# PitchDetector.net
KiCad netlist of a schematic drawn in EAGLE
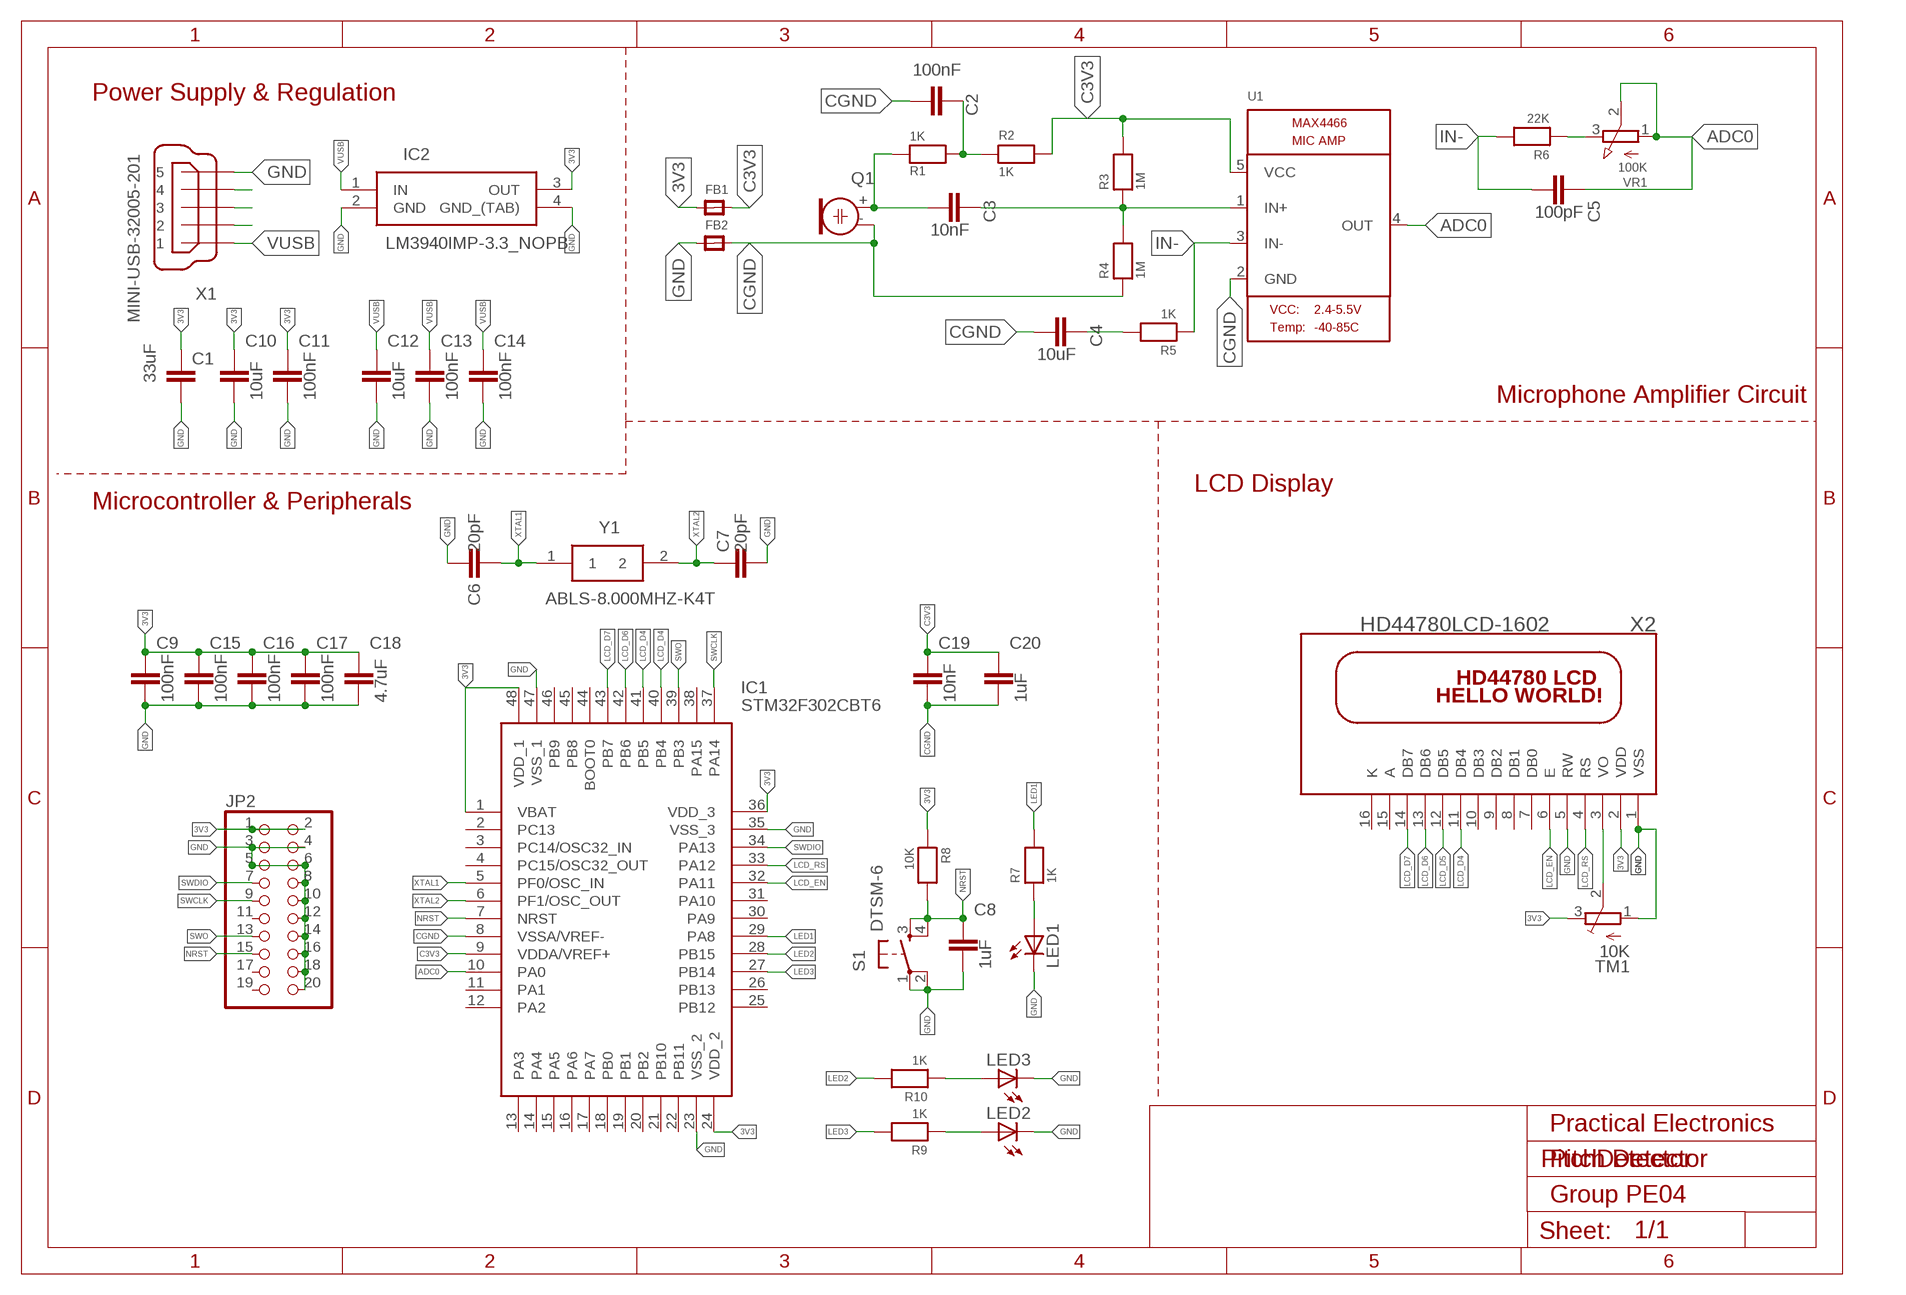
[diagram p0: schematic, sheet 1]

(export (version "E")
  (design (tool "Eeschema 10.0.6"))
  (components
    (comp (ref "C1")
      (value "33uF")
      (footprint "eagle-import:C1206K")
      (libsource (lib "eagle-import") (part "resistor_348_C-EUC1206K"))
    )
    (comp (ref "C2")
      (value "100nF")
      (footprint "eagle-import:C1206K")
      (libsource (lib "eagle-import") (part "resistor_348_C-EUC1206K"))
    )
    (comp (ref "C3")
      (value "10nF")
      (footprint "eagle-import:C1206K")
      (libsource (lib "eagle-import") (part "resistor_348_C-EUC1206K"))
    )
    (comp (ref "C4")
      (value "10uF")
      (footprint "eagle-import:C1206K")
      (libsource (lib "eagle-import") (part "resistor_348_C-EUC1206K"))
    )
    (comp (ref "C5")
      (value "100pF")
      (footprint "eagle-import:C1206K")
      (libsource (lib "eagle-import") (part "resistor_348_C-EUC1206K"))
    )
    (comp (ref "C6")
      (value "20pF")
      (footprint "eagle-import:C0805K")
      (libsource (lib "eagle-import") (part "C-EUC0805K"))
    )
    (comp (ref "C7")
      (value "20pF")
      (footprint "eagle-import:C0805K")
      (libsource (lib "eagle-import") (part "C-EUC0805K"))
    )
    (comp (ref "C8")
      (value "1uF")
      (footprint "eagle-import:C1206K")
      (libsource (lib "eagle-import") (part "resistor_348_C-EUC1206K"))
    )
    (comp (ref "C9")
      (value "100nF")
      (footprint "eagle-import:C1206K")
      (libsource (lib "eagle-import") (part "resistor_348_C-EUC1206K"))
    )
    (comp (ref "C10")
      (value "10uF")
      (footprint "eagle-import:C1206K")
      (libsource (lib "eagle-import") (part "resistor_348_C-EUC1206K"))
    )
    (comp (ref "C11")
      (value "100nF")
      (footprint "eagle-import:C1206K")
      (libsource (lib "eagle-import") (part "resistor_348_C-EUC1206K"))
    )
    (comp (ref "C12")
      (value "10uF")
      (footprint "eagle-import:C1206K")
      (libsource (lib "eagle-import") (part "resistor_348_C-EUC1206K"))
    )
    (comp (ref "C13")
      (value "100nF")
      (footprint "eagle-import:C1206K")
      (libsource (lib "eagle-import") (part "resistor_348_C-EUC1206K"))
    )
    (comp (ref "C14")
      (value "100nF")
      (footprint "eagle-import:C1206K")
      (libsource (lib "eagle-import") (part "resistor_348_C-EUC1206K"))
    )
    (comp (ref "C15")
      (value "100nF")
      (footprint "eagle-import:C1206K")
      (libsource (lib "eagle-import") (part "resistor_348_C-EUC1206K"))
    )
    (comp (ref "C16")
      (value "100nF")
      (footprint "eagle-import:C1206K")
      (libsource (lib "eagle-import") (part "resistor_348_C-EUC1206K"))
    )
    (comp (ref "C17")
      (value "100nF")
      (footprint "eagle-import:C1206K")
      (libsource (lib "eagle-import") (part "resistor_348_C-EUC1206K"))
    )
    (comp (ref "C18")
      (value "4.7uF")
      (footprint "eagle-import:C1206K")
      (libsource (lib "eagle-import") (part "resistor_348_C-EUC1206K"))
    )
    (comp (ref "C19")
      (value "10nF")
      (footprint "eagle-import:C1206K")
      (libsource (lib "eagle-import") (part "resistor_348_C-EUC1206K"))
    )
    (comp (ref "C20")
      (value "1uF")
      (footprint "eagle-import:C1206K")
      (libsource (lib "eagle-import") (part "resistor_348_C-EUC1206K"))
    )
    (comp (ref "FB1")
      (value "MICROBUILDER_FERRITE_0805")
      (footprint "eagle-import:MICROBUILDER__0805")
      (libsource (lib "eagle-import") (part "MICROBUILDER_FERRITE_0805"))
    )
    (comp (ref "FB2")
      (value "MICROBUILDER_FERRITE_0805")
      (footprint "eagle-import:MICROBUILDER__0805")
      (libsource (lib "eagle-import") (part "MICROBUILDER_FERRITE_0805"))
    )
    (comp (ref "IC1")
      (value "STM32F302CBT6")
      (footprint "eagle-import:QFP50P900X900X160-48N")
      (fields
        (field (name "MOUSER_PART_NUMBER") "511-STM32F302CBT6")
        (field (name "RS_PART_NUMBER") "8107641P")
      )
      (libsource (lib "eagle-import") (part "STM32F302CBT6"))
    )
    (comp (ref "IC2")
      (value "LM3940IMP-3.3_NOPB")
      (footprint "eagle-import:SOT230P700X180-4N")
      (fields
        (field (name "MANUFACTURER_PART_NUMBER") "LM3940IMP-3.3/NOPB")
        (field (name "MOUSER_PART_NUMBER") "926-LM3940IMP3.3NOPB")
      )
      (libsource (lib "eagle-import") (part "LM3940IMP-3.3_NOPB"))
    )
    (comp (ref "JP2")
      (value "PINHD-2X10")
      (footprint "eagle-import:2X10")
      (libsource (lib "eagle-import") (part "PINHD-2X10"))
    )
    (comp (ref "LED1")
      (value "LEDCHIPLED_1206")
      (footprint "eagle-import:CHIPLED_1206")
      (libsource (lib "eagle-import") (part "LEDCHIPLED_1206"))
    )
    (comp (ref "LED2")
      (value "LEDCHIPLED_1206")
      (footprint "eagle-import:CHIPLED_1206")
      (libsource (lib "eagle-import") (part "LEDCHIPLED_1206"))
    )
    (comp (ref "LED3")
      (value "LEDCHIPLED_1206")
      (footprint "eagle-import:CHIPLED_1206")
      (libsource (lib "eagle-import") (part "LEDCHIPLED_1206"))
    )
    (comp (ref "Q1")
      (value "MICROBUILDER_ELECTRET")
      (footprint "eagle-import:MICROBUILDER_ELECTRET_9.7")
      (libsource (lib "eagle-import") (part "MICROBUILDER_ELECTRET"))
    )
    (comp (ref "R1")
      (value "1K")
      (footprint "eagle-import:MICROBUILDER_1206")
      (libsource (lib "eagle-import") (part "MICROBUILDER_RESISTOR1206"))
    )
    (comp (ref "R2")
      (value "1K")
      (footprint "eagle-import:MICROBUILDER_1206")
      (libsource (lib "eagle-import") (part "MICROBUILDER_RESISTOR1206"))
    )
    (comp (ref "R3")
      (value "1M")
      (footprint "eagle-import:MICROBUILDER_1206")
      (libsource (lib "eagle-import") (part "MICROBUILDER_RESISTOR1206"))
    )
    (comp (ref "R4")
      (value "1M")
      (footprint "eagle-import:MICROBUILDER_1206")
      (libsource (lib "eagle-import") (part "MICROBUILDER_RESISTOR1206"))
    )
    (comp (ref "R5")
      (value "1K")
      (footprint "eagle-import:MICROBUILDER_1206")
      (libsource (lib "eagle-import") (part "MICROBUILDER_RESISTOR1206"))
    )
    (comp (ref "R6")
      (value "22K")
      (footprint "eagle-import:MICROBUILDER_1206")
      (libsource (lib "eagle-import") (part "MICROBUILDER_RESISTOR1206"))
    )
    (comp (ref "R7")
      (value "1K")
      (footprint "eagle-import:MICROBUILDER_1206")
      (libsource (lib "eagle-import") (part "MICROBUILDER_RESISTOR1206"))
    )
    (comp (ref "R8")
      (value "10K")
      (footprint "eagle-import:MICROBUILDER_1206")
      (libsource (lib "eagle-import") (part "MICROBUILDER_RESISTOR1206"))
    )
    (comp (ref "R9")
      (value "1K")
      (footprint "eagle-import:MICROBUILDER_1206")
      (libsource (lib "eagle-import") (part "MICROBUILDER_RESISTOR1206"))
    )
    (comp (ref "R10")
      (value "1K")
      (footprint "eagle-import:MICROBUILDER_1206")
      (libsource (lib "eagle-import") (part "MICROBUILDER_RESISTOR1206"))
    )
    (comp (ref "S1")
      (value "DTSM-6")
      (footprint "eagle-import:DTSM-6")
      (libsource (lib "eagle-import") (part "DTSM-6"))
    )
    (comp (ref "TM1")
      (value "10K")
      (footprint "eagle-import:TC33X")
      (libsource (lib "eagle-import") (part "TRIMPOTTC33X"))
    )
    (comp (ref "U1")
      (value "MICROBUILDER_MAX4466\"\"")
      (footprint "eagle-import:MICROBUILDER_SC70-5")
      (libsource (lib "eagle-import") (part "MICROBUILDER_MAX4466{dblquote}{dblquote}"))
    )
    (comp (ref "VR1")
      (value "100K")
      (footprint "eagle-import:MICROBUILDER_TRIMPOT_BOURNS_TC33X-2")
      (libsource (lib "eagle-import") (part "MICROBUILDER_TRIMPOTTC33X-2"))
    )
    (comp (ref "X1")
      (value "MINI-USB-32005-201")
      (footprint "eagle-import:32005-201")
      (libsource (lib "eagle-import") (part "MINI-USB-32005-201"))
    )
    (comp (ref "X2")
      (value "HD44780LCD-1602")
      (footprint "eagle-import:LCD1602")
      (libsource (lib "eagle-import") (part "HD44780LCD-1602"))
    )
    (comp (ref "Y1")
      (value "ABLS-8.000MHZ-K4T")
      (footprint "eagle-import:ABLS-12.000MHZ-B2")
      (fields (field (name "MOUSER_PART_NUMBER") "815-ABLS-8.0MK4-T"))
      (libsource (lib "eagle-import") (part "ABLS-8.000MHZ-K4T"))
    )
  )
  (nets
    (net (code "1") (name "3V3") (class "Default")
      (node (ref "C1") (pin "1") (pinfunction "1_1") (pintype "passive"))
      (node (ref "C10") (pin "1") (pinfunction "1_1") (pintype "passive"))
      (node (ref "C11") (pin "1") (pinfunction "1_1") (pintype "passive"))
      (node (ref "C15") (pin "1") (pinfunction "1_1") (pintype "passive"))
      (node (ref "C16") (pin "1") (pinfunction "1_1") (pintype "passive"))
      (node (ref "C17") (pin "1") (pinfunction "1_1") (pintype "passive"))
      (node (ref "C18") (pin "1") (pinfunction "1_1") (pintype "passive"))
      (node (ref "C9") (pin "1") (pinfunction "1_1") (pintype "passive"))
      (node (ref "FB1") (pin "1") (pinfunction "P$1_1") (pintype "passive"))
      (node (ref "IC1") (pin "1") (pinfunction "VBAT_1") (pintype "bidirectional"))
      (node (ref "IC1") (pin "24") (pinfunction "VDD_2_24") (pintype "power_in"))
      (node (ref "IC1") (pin "36") (pinfunction "VDD_3_36") (pintype "power_in"))
      (node (ref "IC1") (pin "48") (pinfunction "VDD_1_48") (pintype "power_in"))
      (node (ref "IC2") (pin "3") (pinfunction "OUT_3") (pintype "output"))
      (node (ref "JP2") (pin "1") (pinfunction "1_1") (pintype "passive"))
      (node (ref "JP2") (pin "2") (pinfunction "2_2") (pintype "passive"))
      (node (ref "R8") (pin "1") (pinfunction "1_1") (pintype "passive"))
      (node (ref "TM1") (pin "3") (pinfunction "E_3") (pintype "passive"))
      (node (ref "X2") (pin "2") (pinfunction "VDD_2") (pintype "power_in"))
    )
    (net (code "2") (name "ADC0") (class "Default")
      (node (ref "C5") (pin "1") (pinfunction "1_1") (pintype "passive"))
      (node (ref "IC1") (pin "10") (pinfunction "PA0_10") (pintype "bidirectional"))
      (node (ref "U1") (pin "4") (pinfunction "OUT_4") (pintype "bidirectional"))
      (node (ref "VR1") (pin "1") (pinfunction "A_1") (pintype "passive"))
      (node (ref "VR1") (pin "2") (pinfunction "S_2") (pintype "passive"))
    )
    (net (code "3") (name "C3V3") (class "Default")
      (node (ref "C19") (pin "1") (pinfunction "1_1") (pintype "passive"))
      (node (ref "C20") (pin "1") (pinfunction "1_1") (pintype "passive"))
      (node (ref "FB1") (pin "2") (pinfunction "P$2_2") (pintype "passive"))
      (node (ref "IC1") (pin "9") (pinfunction "VDDA/VREF+_9") (pintype "power_in"))
      (node (ref "R2") (pin "2") (pinfunction "2_2") (pintype "passive"))
      (node (ref "R3") (pin "2") (pinfunction "2_2") (pintype "passive"))
      (node (ref "U1") (pin "5") (pinfunction "VCC_5") (pintype "bidirectional"))
    )
    (net (code "4") (name "CGND") (class "Default")
      (node (ref "C19") (pin "2") (pinfunction "2_2") (pintype "passive"))
      (node (ref "C2") (pin "2") (pinfunction "2_2") (pintype "passive"))
      (node (ref "C20") (pin "2") (pinfunction "2_2") (pintype "passive"))
      (node (ref "C4") (pin "2") (pinfunction "2_2") (pintype "passive"))
      (node (ref "FB2") (pin "2") (pinfunction "P$2_2") (pintype "passive"))
      (node (ref "IC1") (pin "8") (pinfunction "VSSA/VREF-_8") (pintype "power_in"))
      (node (ref "Q1") (pin "-") (pinfunction "1_-") (pintype "passive"))
      (node (ref "R4") (pin "1") (pinfunction "1_1") (pintype "passive"))
      (node (ref "U1") (pin "2") (pinfunction "GND_2") (pintype "bidirectional"))
    )
    (net (code "5") (name "GND") (class "Default")
      (node (ref "C1") (pin "2") (pinfunction "2_2") (pintype "passive"))
      (node (ref "C10") (pin "2") (pinfunction "2_2") (pintype "passive"))
      (node (ref "C11") (pin "2") (pinfunction "2_2") (pintype "passive"))
      (node (ref "C12") (pin "2") (pinfunction "2_2") (pintype "passive"))
      (node (ref "C13") (pin "2") (pinfunction "2_2") (pintype "passive"))
      (node (ref "C14") (pin "2") (pinfunction "2_2") (pintype "passive"))
      (node (ref "C15") (pin "2") (pinfunction "2_2") (pintype "passive"))
      (node (ref "C16") (pin "2") (pinfunction "2_2") (pintype "passive"))
      (node (ref "C17") (pin "2") (pinfunction "2_2") (pintype "passive"))
      (node (ref "C18") (pin "2") (pinfunction "2_2") (pintype "passive"))
      (node (ref "C6") (pin "1") (pinfunction "1_1") (pintype "passive"))
      (node (ref "C7") (pin "2") (pinfunction "2_2") (pintype "passive"))
      (node (ref "C8") (pin "2") (pinfunction "2_2") (pintype "passive"))
      (node (ref "C9") (pin "2") (pinfunction "2_2") (pintype "passive"))
      (node (ref "FB2") (pin "1") (pinfunction "P$1_1") (pintype "passive"))
      (node (ref "IC1") (pin "23") (pinfunction "VSS_2_23") (pintype "power_in"))
      (node (ref "IC1") (pin "35") (pinfunction "VSS_3_35") (pintype "power_in"))
      (node (ref "IC1") (pin "47") (pinfunction "VSS_1_47") (pintype "power_in"))
      (node (ref "IC2") (pin "2") (pinfunction "GND_2") (pintype "power_in"))
      (node (ref "IC2") (pin "4") (pinfunction "GND_(TAB)_4") (pintype "power_in"))
      (node (ref "JP2") (pin "10") (pinfunction "10_10") (pintype "passive"))
      (node (ref "JP2") (pin "12") (pinfunction "12_12") (pintype "passive"))
      (node (ref "JP2") (pin "14") (pinfunction "14_14") (pintype "passive"))
      (node (ref "JP2") (pin "16") (pinfunction "16_16") (pintype "passive"))
      (node (ref "JP2") (pin "18") (pinfunction "18_18") (pintype "passive"))
      (node (ref "JP2") (pin "20") (pinfunction "20_20") (pintype "passive"))
      (node (ref "JP2") (pin "3") (pinfunction "3_3") (pintype "passive"))
      (node (ref "JP2") (pin "4") (pinfunction "4_4") (pintype "passive"))
      (node (ref "JP2") (pin "5") (pinfunction "5_5") (pintype "passive"))
      (node (ref "JP2") (pin "6") (pinfunction "6_6") (pintype "passive"))
      (node (ref "JP2") (pin "8") (pinfunction "8_8") (pintype "passive"))
      (node (ref "LED1") (pin "C") (pinfunction "C_C") (pintype "passive"))
      (node (ref "LED2") (pin "C") (pinfunction "C_C") (pintype "passive"))
      (node (ref "LED3") (pin "C") (pinfunction "C_C") (pintype "passive"))
      (node (ref "S1") (pin "1") (pinfunction "1_1") (pintype "passive"))
      (node (ref "S1") (pin "2") (pinfunction "2_2") (pintype "passive"))
      (node (ref "TM1") (pin "1") (pinfunction "A_1") (pintype "passive"))
      (node (ref "X1") (pin "5") (pinfunction "5_5") (pintype "passive"))
      (node (ref "X2") (pin "1") (pinfunction "VSS_1") (pintype "power_in"))
      (node (ref "X2") (pin "5") (pinfunction "RW_5") (pintype "input"))
    )
    (net (code "6") (name "IN-") (class "Default")
      (node (ref "C5") (pin "2") (pinfunction "2_2") (pintype "passive"))
      (node (ref "R5") (pin "1") (pinfunction "1_1") (pintype "passive"))
      (node (ref "R6") (pin "2") (pinfunction "2_2") (pintype "passive"))
      (node (ref "U1") (pin "3") (pinfunction "IN-_3") (pintype "bidirectional"))
    )
    (net (code "7") (name "LCD_D4") (class "Default")
      (node (ref "IC1") (pin "40") (pinfunction "PB4_40") (pintype "bidirectional"))
      (node (ref "IC1") (pin "41") (pinfunction "PB5_41") (pintype "bidirectional"))
      (node (ref "X2") (pin "11") (pinfunction "DB4_11") (pintype "bidirectional"))
    )
    (net (code "8") (name "LCD_D5") (class "Default")
      (node (ref "X2") (pin "12") (pinfunction "DB5_12") (pintype "bidirectional"))
    )
    (net (code "9") (name "LCD_D6") (class "Default")
      (node (ref "IC1") (pin "42") (pinfunction "PB6_42") (pintype "bidirectional"))
      (node (ref "X2") (pin "13") (pinfunction "DB6_13") (pintype "bidirectional"))
    )
    (net (code "10") (name "LCD_D7") (class "Default")
      (node (ref "IC1") (pin "43") (pinfunction "PB7_43") (pintype "bidirectional"))
      (node (ref "X2") (pin "14") (pinfunction "DB7_14") (pintype "bidirectional"))
    )
    (net (code "11") (name "LCD_EN") (class "Default")
      (node (ref "IC1") (pin "32") (pinfunction "PA11_32") (pintype "bidirectional"))
      (node (ref "X2") (pin "6") (pinfunction "E_6") (pintype "input"))
    )
    (net (code "12") (name "LCD_RS") (class "Default")
      (node (ref "IC1") (pin "33") (pinfunction "PA12_33") (pintype "bidirectional"))
      (node (ref "X2") (pin "4") (pinfunction "RS_4") (pintype "input"))
    )
    (net (code "13") (name "LED1") (class "Default")
      (node (ref "IC1") (pin "29") (pinfunction "PA8_29") (pintype "bidirectional"))
      (node (ref "R7") (pin "2") (pinfunction "2_2") (pintype "passive"))
    )
    (net (code "14") (name "LED2") (class "Default")
      (node (ref "IC1") (pin "28") (pinfunction "PB15_28") (pintype "bidirectional"))
      (node (ref "R10") (pin "2") (pinfunction "2_2") (pintype "passive"))
    )
    (net (code "15") (name "LED3") (class "Default")
      (node (ref "IC1") (pin "27") (pinfunction "PB14_27") (pintype "bidirectional"))
      (node (ref "R9") (pin "2") (pinfunction "2_2") (pintype "passive"))
    )
    (net (code "16") (name "NRST") (class "Default")
      (node (ref "C8") (pin "1") (pinfunction "1_1") (pintype "passive"))
      (node (ref "IC1") (pin "7") (pinfunction "NRST_7") (pintype "input"))
      (node (ref "JP2") (pin "15") (pinfunction "15_15") (pintype "passive"))
      (node (ref "R8") (pin "2") (pinfunction "2_2") (pintype "passive"))
      (node (ref "S1") (pin "3") (pinfunction "3_3") (pintype "passive"))
      (node (ref "S1") (pin "4") (pinfunction "4_4") (pintype "passive"))
    )
    (net (code "17") (name "Net-(C2-Pad1)") (class "Default")
      (node (ref "C2") (pin "1") (pinfunction "1_1") (pintype "passive"))
      (node (ref "R1") (pin "2") (pinfunction "2_2") (pintype "passive"))
      (node (ref "R2") (pin "1") (pinfunction "1_1") (pintype "passive"))
    )
    (net (code "18") (name "Net-(C4-Pad1)") (class "Default")
      (node (ref "C4") (pin "1") (pinfunction "1_1") (pintype "passive"))
      (node (ref "R5") (pin "2") (pinfunction "2_2") (pintype "passive"))
    )
    (net (code "19") (name "Net-(LED1-PadA)") (class "Default")
      (node (ref "LED1") (pin "A") (pinfunction "A_A") (pintype "passive"))
      (node (ref "R7") (pin "1") (pinfunction "1_1") (pintype "passive"))
    )
    (net (code "20") (name "Net-(LED2-PadA)") (class "Default")
      (node (ref "LED2") (pin "A") (pinfunction "A_A") (pintype "passive"))
      (node (ref "R9") (pin "1") (pinfunction "1_1") (pintype "passive"))
    )
    (net (code "21") (name "Net-(LED3-PadA)") (class "Default")
      (node (ref "LED3") (pin "A") (pinfunction "A_A") (pintype "passive"))
      (node (ref "R10") (pin "1") (pinfunction "1_1") (pintype "passive"))
    )
    (net (code "22") (name "Net-(Q1-2)") (class "Default")
      (node (ref "C3") (pin "2") (pinfunction "2_2") (pintype "passive"))
      (node (ref "Q1") (pin "+") (pinfunction "2_+") (pintype "passive"))
      (node (ref "R1") (pin "1") (pinfunction "1_1") (pintype "passive"))
    )
    (net (code "23") (name "Net-(TM1-S)") (class "Default")
      (node (ref "TM1") (pin "2") (pinfunction "S_2") (pintype "passive"))
      (node (ref "X2") (pin "3") (pinfunction "VO_3") (pintype "input"))
    )
    (net (code "24") (name "Net-(U1-IN+)") (class "Default")
      (node (ref "C3") (pin "1") (pinfunction "1_1") (pintype "passive"))
      (node (ref "R3") (pin "1") (pinfunction "1_1") (pintype "passive"))
      (node (ref "R4") (pin "2") (pinfunction "2_2") (pintype "passive"))
      (node (ref "U1") (pin "1") (pinfunction "IN+_1") (pintype "bidirectional"))
    )
    (net (code "25") (name "Net-(VR1-E)") (class "Default")
      (node (ref "R6") (pin "1") (pinfunction "1_1") (pintype "passive"))
      (node (ref "VR1") (pin "3") (pinfunction "E_3") (pintype "passive"))
    )
    (net (code "26") (name "SWCLK") (class "Default")
      (node (ref "IC1") (pin "37") (pinfunction "PA14_37") (pintype "bidirectional"))
      (node (ref "JP2") (pin "9") (pinfunction "9_9") (pintype "passive"))
    )
    (net (code "27") (name "SWDIO") (class "Default")
      (node (ref "IC1") (pin "34") (pinfunction "PA13_34") (pintype "bidirectional"))
      (node (ref "JP2") (pin "7") (pinfunction "7_7") (pintype "passive"))
    )
    (net (code "28") (name "SWO") (class "Default")
      (node (ref "IC1") (pin "39") (pinfunction "PB3_39") (pintype "bidirectional"))
      (node (ref "JP2") (pin "13") (pinfunction "13_13") (pintype "passive"))
    )
    (net (code "29") (name "VUSB") (class "Default")
      (node (ref "C12") (pin "1") (pinfunction "1_1") (pintype "passive"))
      (node (ref "C13") (pin "1") (pinfunction "1_1") (pintype "passive"))
      (node (ref "C14") (pin "1") (pinfunction "1_1") (pintype "passive"))
      (node (ref "IC2") (pin "1") (pinfunction "IN_1") (pintype "power_in"))
      (node (ref "X1") (pin "1") (pinfunction "1_1") (pintype "passive"))
    )
    (net (code "30") (name "XTAL1") (class "Default")
      (node (ref "C6") (pin "2") (pinfunction "2_2") (pintype "passive"))
      (node (ref "IC1") (pin "5") (pinfunction "PF0/OSC_IN_5") (pintype "input"))
      (node (ref "Y1") (pin "1") (pinfunction "1_1") (pintype "bidirectional"))
    )
    (net (code "31") (name "XTAL2") (class "Default")
      (node (ref "C7") (pin "1") (pinfunction "1_1") (pintype "passive"))
      (node (ref "IC1") (pin "6") (pinfunction "PF1/OSC_OUT_6") (pintype "output"))
      (node (ref "Y1") (pin "2") (pinfunction "2_2") (pintype "bidirectional"))
    )
    (net (code "32") (name "unconnected-(IC1-BOOT0-Pad44)") (class "Default")
      (node (ref "IC1") (pin "44") (pinfunction "BOOT0_44") (pintype "bidirectional"))
    )
    (net (code "33") (name "unconnected-(IC1-PA1-Pad11)") (class "Default")
      (node (ref "IC1") (pin "11") (pinfunction "PA1_11") (pintype "bidirectional"))
    )
    (net (code "34") (name "unconnected-(IC1-PA2-Pad12)") (class "Default")
      (node (ref "IC1") (pin "12") (pinfunction "PA2_12") (pintype "bidirectional"))
    )
    (net (code "35") (name "unconnected-(IC1-PA3-Pad13)") (class "Default")
      (node (ref "IC1") (pin "13") (pinfunction "PA3_13") (pintype "bidirectional"))
    )
    (net (code "36") (name "unconnected-(IC1-PA4-Pad14)") (class "Default")
      (node (ref "IC1") (pin "14") (pinfunction "PA4_14") (pintype "bidirectional"))
    )
    (net (code "37") (name "unconnected-(IC1-PA5-Pad15)") (class "Default")
      (node (ref "IC1") (pin "15") (pinfunction "PA5_15") (pintype "bidirectional"))
    )
    (net (code "38") (name "unconnected-(IC1-PA6-Pad16)") (class "Default")
      (node (ref "IC1") (pin "16") (pinfunction "PA6_16") (pintype "bidirectional"))
    )
    (net (code "39") (name "unconnected-(IC1-PA7-Pad17)") (class "Default")
      (node (ref "IC1") (pin "17") (pinfunction "PA7_17") (pintype "bidirectional"))
    )
    (net (code "40") (name "unconnected-(IC1-PA9-Pad30)") (class "Default")
      (node (ref "IC1") (pin "30") (pinfunction "PA9_30") (pintype "bidirectional"))
    )
    (net (code "41") (name "unconnected-(IC1-PA10-Pad31)") (class "Default")
      (node (ref "IC1") (pin "31") (pinfunction "PA10_31") (pintype "bidirectional"))
    )
    (net (code "42") (name "unconnected-(IC1-PA15-Pad38)") (class "Default")
      (node (ref "IC1") (pin "38") (pinfunction "PA15_38") (pintype "bidirectional"))
    )
    (net (code "43") (name "unconnected-(IC1-PB0-Pad18)") (class "Default")
      (node (ref "IC1") (pin "18") (pinfunction "PB0_18") (pintype "bidirectional"))
    )
    (net (code "44") (name "unconnected-(IC1-PB1-Pad19)") (class "Default")
      (node (ref "IC1") (pin "19") (pinfunction "PB1_19") (pintype "bidirectional"))
    )
    (net (code "45") (name "unconnected-(IC1-PB2-Pad20)") (class "Default")
      (node (ref "IC1") (pin "20") (pinfunction "PB2_20") (pintype "bidirectional"))
    )
    (net (code "46") (name "unconnected-(IC1-PB8-Pad45)") (class "Default")
      (node (ref "IC1") (pin "45") (pinfunction "PB8_45") (pintype "bidirectional"))
    )
    (net (code "47") (name "unconnected-(IC1-PB9-Pad46)") (class "Default")
      (node (ref "IC1") (pin "46") (pinfunction "PB9_46") (pintype "bidirectional"))
    )
    (net (code "48") (name "unconnected-(IC1-PB10-Pad21)") (class "Default")
      (node (ref "IC1") (pin "21") (pinfunction "PB10_21") (pintype "bidirectional"))
    )
    (net (code "49") (name "unconnected-(IC1-PB11-Pad22)") (class "Default")
      (node (ref "IC1") (pin "22") (pinfunction "PB11_22") (pintype "bidirectional"))
    )
    (net (code "50") (name "unconnected-(IC1-PB12-Pad25)") (class "Default")
      (node (ref "IC1") (pin "25") (pinfunction "PB12_25") (pintype "bidirectional"))
    )
    (net (code "51") (name "unconnected-(IC1-PB13-Pad26)") (class "Default")
      (node (ref "IC1") (pin "26") (pinfunction "PB13_26") (pintype "bidirectional"))
    )
    (net (code "52") (name "unconnected-(IC1-PC13-Pad2)") (class "Default")
      (node (ref "IC1") (pin "2") (pinfunction "PC13_2") (pintype "bidirectional"))
    )
    (net (code "53") (name "unconnected-(IC1-PC14{slash}OSC32_IN-Pad3)") (class "Default")
      (node (ref "IC1") (pin "3") (pinfunction "PC14/OSC32_IN_3") (pintype "input"))
    )
    (net (code "54") (name "unconnected-(IC1-PC15{slash}OSC32_OUT-Pad4)") (class "Default")
      (node (ref "IC1") (pin "4") (pinfunction "PC15/OSC32_OUT_4") (pintype "output"))
    )
    (net (code "55") (name "unconnected-(JP2-Pad11)") (class "Default")
      (node (ref "JP2") (pin "11") (pinfunction "11_11") (pintype "passive"))
    )
    (net (code "56") (name "unconnected-(JP2-Pad17)") (class "Default")
      (node (ref "JP2") (pin "17") (pinfunction "17_17") (pintype "passive"))
    )
    (net (code "57") (name "unconnected-(JP2-Pad19)") (class "Default")
      (node (ref "JP2") (pin "19") (pinfunction "19_19") (pintype "passive"))
    )
    (net (code "58") (name "unconnected-(X1-Pad2)") (class "Default")
      (node (ref "X1") (pin "2") (pinfunction "2_2") (pintype "passive"))
    )
    (net (code "59") (name "unconnected-(X1-Pad3)") (class "Default")
      (node (ref "X1") (pin "3") (pinfunction "3_3") (pintype "passive"))
    )
    (net (code "60") (name "unconnected-(X1-Pad4)") (class "Default")
      (node (ref "X1") (pin "4") (pinfunction "4_4") (pintype "passive"))
    )
    (net (code "61") (name "unconnected-(X2-A-Pad15)") (class "Default")
      (node (ref "X2") (pin "15") (pinfunction "A_15") (pintype "input"))
    )
    (net (code "62") (name "unconnected-(X2-DB0-Pad7)") (class "Default")
      (node (ref "X2") (pin "7") (pinfunction "DB0_7") (pintype "bidirectional"))
    )
    (net (code "63") (name "unconnected-(X2-DB1-Pad8)") (class "Default")
      (node (ref "X2") (pin "8") (pinfunction "DB1_8") (pintype "bidirectional"))
    )
    (net (code "64") (name "unconnected-(X2-DB2-Pad9)") (class "Default")
      (node (ref "X2") (pin "9") (pinfunction "DB2_9") (pintype "bidirectional"))
    )
    (net (code "65") (name "unconnected-(X2-DB3-Pad10)") (class "Default")
      (node (ref "X2") (pin "10") (pinfunction "DB3_10") (pintype "bidirectional"))
    )
    (net (code "66") (name "unconnected-(X2-K-Pad16)") (class "Default")
      (node (ref "X2") (pin "16") (pinfunction "K_16") (pintype "input"))
    )
  )
)
